# DK_GU906_HW_V1.net
KiCad netlist of a schematic drawn in Altium Designer
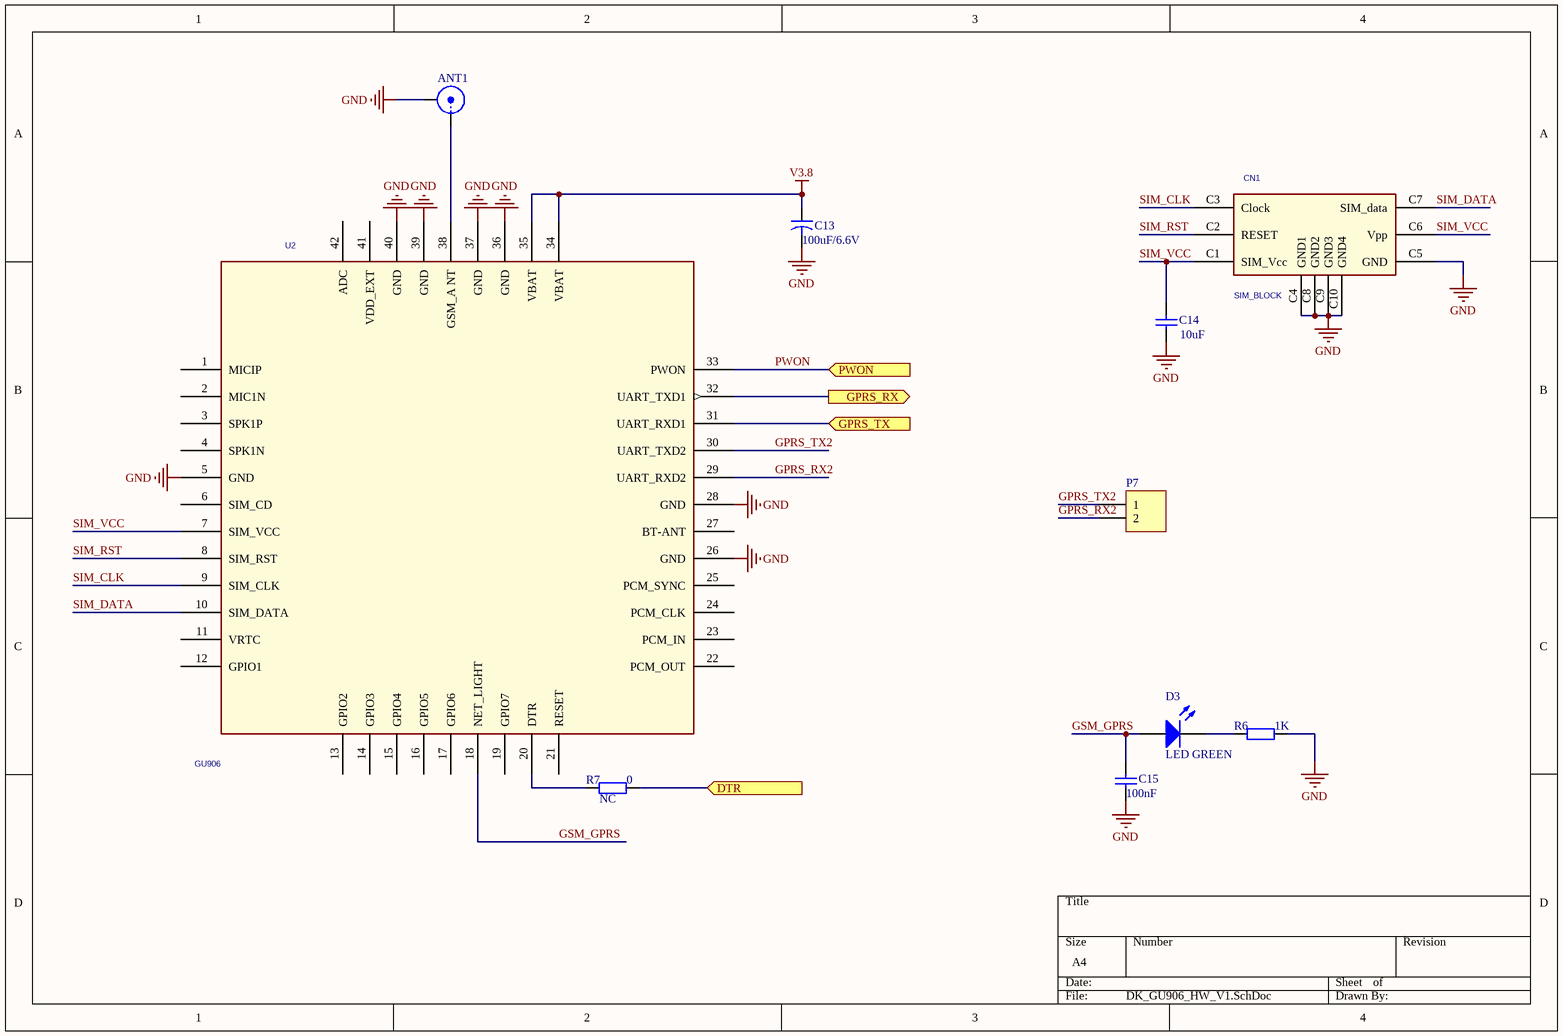
[diagram p0: DK_GU906_HW_V1.SchDoc]

(export (version "E")
  (design (tool "Eeschema 10.0.6"))
  (components
    (comp (ref "ANT1")
      (value "SMB")
      (footprint "SMB_V-RJ45")
      (description "SMB Straight Connector")
      (fields (field (name "PUBLISHER") "Altium Limited"))
      (libsource (lib "Miscellaneous Connectors") (part "SMB"))
    )
    (comp (ref "C13")
      (value "100uF/6.6V")
      (footprint "0603")
      (description "Capacitor")
      (fields (field (name "Comment") "Cap2") (field (name "PUBLISHER") "Altium Limited"))
      (libsource (lib "Miscellaneous Devices") (part "Cap2"))
    )
    (comp (ref "C14")
      (value "10uF")
      (footprint "0603")
      (description "Capacitor")
      (fields (field (name "Comment") "Cap") (field (name "PUBLISHER") "Altium Limited"))
      (libsource (lib "Miscellaneous Devices") (part "Cap"))
    )
    (comp (ref "C15")
      (value "100nF")
      (footprint "0603")
      (description "Capacitor")
      (fields (field (name "Comment") "Cap") (field (name "PUBLISHER") "Altium Limited"))
      (libsource (lib "Miscellaneous Devices") (part "Cap"))
    )
    (comp (ref "CN1")
      (value "SIM_BLOCK")
      (footprint "SIM_BLOCK")
      (libsource (lib "TB906") (part "SIM_BLOCK_2"))
    )
    (comp (ref "D3")
      (value "LED GREEN")
      (footprint "LED0603")
      (description "Typical RED, GREEN, YELLOW, AMBER GaAs LED")
      (fields (field (name "PUBLISHER") "Altium Limited"))
      (libsource (lib "Miscellaneous Devices") (part "LED2"))
    )
    (comp (ref "P7")
      (value "Header 2")
      (footprint "HDR1X2")
      (description "Header, 2-Pin")
      (fields (field (name "PUBLISHER") "Altium Limited"))
      (libsource (lib "Miscellaneous Connectors") (part "Header 2"))
    )
    (comp (ref "R6")
      (value "1K")
      (footprint "0603")
      (description "Resistor")
      (fields (field (name "Comment") "Res2") (field (name "PUBLISHER") "Altium Limited"))
      (libsource (lib "Miscellaneous Devices") (part "Res2"))
    )
    (comp (ref "R7")
      (value "NC")
      (footprint "0603")
      (description "Resistor")
      (fields (field (name "ALTIUM_VALUE") "0") (field (name "PUBLISHER") "Altium Limited"))
      (libsource (lib "Miscellaneous Devices") (part "Res2"))
    )
    (comp (ref "U2") (value "GU906") (libsource (lib "TB906") (part "GU600_LIB_2")))
  )
  (nets
    (net (code "1") (name "/DTR") (class "Default")
      (node (ref "R7") (pin "2") (pinfunction "2_2") (pintype "passive"))
    )
    (net (code "2") (name "/GPRS_RX") (class "Default")
      (node (ref "U2") (pin "32") (pinfunction "UART_TXD1_32") (pintype "output"))
    )
    (net (code "3") (name "/GPRS_RX2") (class "Default")
      (node (ref "P7") (pin "2") (pinfunction "2_2") (pintype "passive"))
      (node (ref "U2") (pin "29") (pinfunction "UART_RXD2_29") (pintype "passive"))
    )
    (net (code "4") (name "/GPRS_TX") (class "Default")
      (node (ref "U2") (pin "31") (pinfunction "UART_RXD1_31") (pintype "passive"))
    )
    (net (code "5") (name "/GPRS_TX2") (class "Default")
      (node (ref "P7") (pin "1") (pinfunction "1_1") (pintype "passive"))
      (node (ref "U2") (pin "30") (pinfunction "UART_TXD2_30") (pintype "passive"))
    )
    (net (code "6") (name "/GSM_GPRS") (class "Default")
      (node (ref "C15") (pin "2") (pinfunction "2_2") (pintype "passive"))
      (node (ref "D3") (pin "1") (pinfunction "A_1") (pintype "passive"))
      (node (ref "U2") (pin "18") (pinfunction "NET_LIGHT_18") (pintype "passive"))
    )
    (net (code "7") (name "/PWON") (class "Default")
      (node (ref "U2") (pin "33") (pinfunction "PWON_33") (pintype "passive"))
    )
    (net (code "8") (name "/SIM_CLK") (class "Default")
      (node (ref "CN1") (pin "C3") (pinfunction "Clock_C3") (pintype "passive"))
      (node (ref "U2") (pin "9") (pinfunction "SIM_CLK_9") (pintype "passive"))
    )
    (net (code "9") (name "/SIM_DATA") (class "Default")
      (node (ref "CN1") (pin "C7") (pinfunction "SIM_data_C7") (pintype "passive"))
      (node (ref "U2") (pin "10") (pinfunction "SIM_DATA_10") (pintype "passive"))
    )
    (net (code "10") (name "/SIM_RST") (class "Default")
      (node (ref "CN1") (pin "C2") (pinfunction "RESET_C2") (pintype "passive"))
      (node (ref "U2") (pin "8") (pinfunction "SIM_RST_8") (pintype "passive"))
    )
    (net (code "11") (name "/SIM_VCC") (class "Default")
      (node (ref "C14") (pin "2") (pinfunction "2_2") (pintype "passive"))
      (node (ref "CN1") (pin "C1") (pinfunction "SIM_Vcc_C1") (pintype "passive"))
      (node (ref "CN1") (pin "C6") (pinfunction "Vpp_C6") (pintype "passive"))
      (node (ref "U2") (pin "7") (pinfunction "SIM_VCC_7") (pintype "passive"))
    )
    (net (code "12") (name "GND") (class "Default")
      (node (ref "ANT1") (pin "2") (pinfunction "Y_2") (pintype "passive"))
      (node (ref "C13") (pin "2") (pinfunction "2_2") (pintype "passive"))
      (node (ref "C14") (pin "1") (pinfunction "1_1") (pintype "passive"))
      (node (ref "C15") (pin "1") (pinfunction "1_1") (pintype "passive"))
      (node (ref "CN1") (pin "C10") (pinfunction "GND4_C10") (pintype "passive"))
      (node (ref "CN1") (pin "C4") (pinfunction "GND1_C4") (pintype "passive"))
      (node (ref "CN1") (pin "C5") (pinfunction "GND_C5") (pintype "passive"))
      (node (ref "CN1") (pin "C8") (pinfunction "GND2_C8") (pintype "passive"))
      (node (ref "CN1") (pin "C9") (pinfunction "GND3_C9") (pintype "passive"))
      (node (ref "R6") (pin "2") (pinfunction "2_2") (pintype "passive"))
      (node (ref "U2") (pin "26") (pinfunction "GND_26") (pintype "passive"))
      (node (ref "U2") (pin "28") (pinfunction "GND_28") (pintype "passive"))
      (node (ref "U2") (pin "36") (pinfunction "GND_36") (pintype "passive"))
      (node (ref "U2") (pin "37") (pinfunction "GND_37") (pintype "passive"))
      (node (ref "U2") (pin "39") (pinfunction "GND_39") (pintype "passive"))
      (node (ref "U2") (pin "40") (pinfunction "GND_40") (pintype "passive"))
      (node (ref "U2") (pin "5") (pinfunction "GND_5") (pintype "passive"))
    )
    (net (code "13") (name "Net-(ANT1-X)") (class "Default")
      (node (ref "ANT1") (pin "1") (pinfunction "X_1") (pintype "passive"))
      (node (ref "U2") (pin "38") (pinfunction "GSM_A_NT_38") (pintype "passive"))
    )
    (net (code "14") (name "Net-(D3-K)") (class "Default")
      (node (ref "D3") (pin "2") (pinfunction "K_2") (pintype "passive"))
      (node (ref "R6") (pin "1") (pinfunction "1_1") (pintype "passive"))
    )
    (net (code "15") (name "Net-(U2-DTR)") (class "Default")
      (node (ref "R7") (pin "1") (pinfunction "1_1") (pintype "passive"))
      (node (ref "U2") (pin "20") (pinfunction "DTR_20") (pintype "passive"))
    )
    (net (code "16") (name "V3.8") (class "Default")
      (node (ref "C13") (pin "1") (pinfunction "1_1") (pintype "passive"))
      (node (ref "U2") (pin "34") (pinfunction "VBAT_34") (pintype "passive"))
      (node (ref "U2") (pin "35") (pinfunction "VBAT_35") (pintype "passive"))
    )
    (net (code "17") (name "unconnected-(U2-ADC-Pad42)") (class "Default")
      (node (ref "U2") (pin "42") (pinfunction "ADC_42") (pintype "passive"))
    )
    (net (code "18") (name "unconnected-(U2-BT-ANT-Pad27)") (class "Default")
      (node (ref "U2") (pin "27") (pinfunction "BT-ANT_27") (pintype "passive"))
    )
    (net (code "19") (name "unconnected-(U2-GPIO1-Pad12)") (class "Default")
      (node (ref "U2") (pin "12") (pinfunction "GPIO1_12") (pintype "passive"))
    )
    (net (code "20") (name "unconnected-(U2-GPIO2-Pad13)") (class "Default")
      (node (ref "U2") (pin "13") (pinfunction "GPIO2_13") (pintype "passive"))
    )
    (net (code "21") (name "unconnected-(U2-GPIO3-Pad14)") (class "Default")
      (node (ref "U2") (pin "14") (pinfunction "GPIO3_14") (pintype "passive"))
    )
    (net (code "22") (name "unconnected-(U2-GPIO4-Pad15)") (class "Default")
      (node (ref "U2") (pin "15") (pinfunction "GPIO4_15") (pintype "passive"))
    )
    (net (code "23") (name "unconnected-(U2-GPIO5-Pad16)") (class "Default")
      (node (ref "U2") (pin "16") (pinfunction "GPIO5_16") (pintype "passive"))
    )
    (net (code "24") (name "unconnected-(U2-GPIO6-Pad17)") (class "Default")
      (node (ref "U2") (pin "17") (pinfunction "GPIO6_17") (pintype "passive"))
    )
    (net (code "25") (name "unconnected-(U2-GPIO7-Pad19)") (class "Default")
      (node (ref "U2") (pin "19") (pinfunction "GPIO7_19") (pintype "passive"))
    )
    (net (code "26") (name "unconnected-(U2-MIC1N-Pad2)") (class "Default")
      (node (ref "U2") (pin "2") (pinfunction "MIC1N_2") (pintype "passive"))
    )
    (net (code "27") (name "unconnected-(U2-MICIP-Pad1)") (class "Default")
      (node (ref "U2") (pin "1") (pinfunction "MICIP_1") (pintype "passive"))
    )
    (net (code "28") (name "unconnected-(U2-PCM_CLK-Pad24)") (class "Default")
      (node (ref "U2") (pin "24") (pinfunction "PCM_CLK_24") (pintype "passive"))
    )
    (net (code "29") (name "unconnected-(U2-PCM_IN-Pad23)") (class "Default")
      (node (ref "U2") (pin "23") (pinfunction "PCM_IN_23") (pintype "passive"))
    )
    (net (code "30") (name "unconnected-(U2-PCM_OUT-Pad22)") (class "Default")
      (node (ref "U2") (pin "22") (pinfunction "PCM_OUT_22") (pintype "passive"))
    )
    (net (code "31") (name "unconnected-(U2-PCM_SYNC-Pad25)") (class "Default")
      (node (ref "U2") (pin "25") (pinfunction "PCM_SYNC_25") (pintype "passive"))
    )
    (net (code "32") (name "unconnected-(U2-RESET-Pad21)") (class "Default")
      (node (ref "U2") (pin "21") (pinfunction "RESET_21") (pintype "passive"))
    )
    (net (code "33") (name "unconnected-(U2-SIM_CD-Pad6)") (class "Default")
      (node (ref "U2") (pin "6") (pinfunction "SIM_CD_6") (pintype "passive"))
    )
    (net (code "34") (name "unconnected-(U2-SPK1N-Pad4)") (class "Default")
      (node (ref "U2") (pin "4") (pinfunction "SPK1N_4") (pintype "passive"))
    )
    (net (code "35") (name "unconnected-(U2-SPK1P-Pad3)") (class "Default")
      (node (ref "U2") (pin "3") (pinfunction "SPK1P_3") (pintype "passive"))
    )
    (net (code "36") (name "unconnected-(U2-VDD_EXT-Pad41)") (class "Default")
      (node (ref "U2") (pin "41") (pinfunction "VDD_EXT_41") (pintype "passive"))
    )
    (net (code "37") (name "unconnected-(U2-VRTC-Pad11)") (class "Default")
      (node (ref "U2") (pin "11") (pinfunction "VRTC_11") (pintype "passive"))
    )
  )
)
